# x15.net
KiCad netlist of a schematic drawn in EAGLE
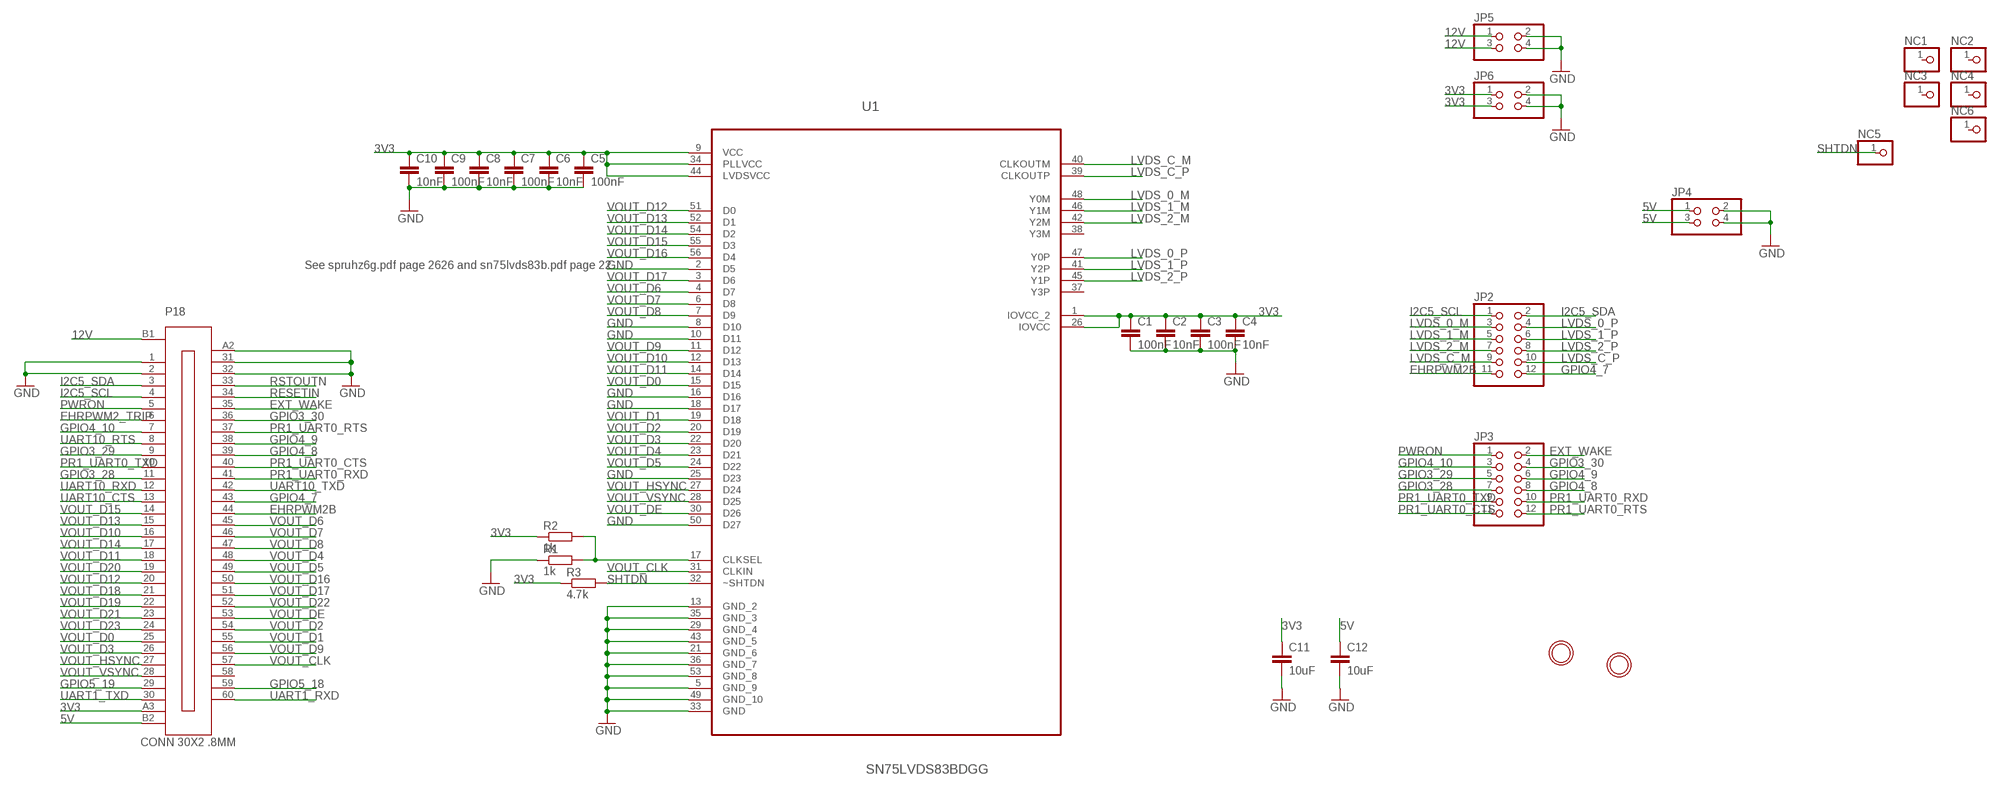
[diagram p0: schematic, sheet 1]

(export (version "E")
  (design (tool "Eeschema 10.0.6"))
  (components
    (comp (ref "C1")
      (value "100nF")
      (footprint "eagle-import:C0603K")
      (libsource (lib "eagle-import") (part "C-EUC0603K"))
    )
    (comp (ref "C2")
      (value "10nF")
      (footprint "eagle-import:C0603K")
      (libsource (lib "eagle-import") (part "C-EUC0603K"))
    )
    (comp (ref "C3")
      (value "100nF")
      (footprint "eagle-import:C0603K")
      (libsource (lib "eagle-import") (part "C-EUC0603K"))
    )
    (comp (ref "C4")
      (value "10nF")
      (footprint "eagle-import:C0603K")
      (libsource (lib "eagle-import") (part "C-EUC0603K"))
    )
    (comp (ref "C5")
      (value "100nF")
      (footprint "eagle-import:C0603K")
      (libsource (lib "eagle-import") (part "C-EUC0603K"))
    )
    (comp (ref "C6")
      (value "10nF")
      (footprint "eagle-import:C0603K")
      (libsource (lib "eagle-import") (part "C-EUC0603K"))
    )
    (comp (ref "C7")
      (value "100nF")
      (footprint "eagle-import:C0603K")
      (libsource (lib "eagle-import") (part "C-EUC0603K"))
    )
    (comp (ref "C8")
      (value "10nF")
      (footprint "eagle-import:C0603K")
      (libsource (lib "eagle-import") (part "C-EUC0603K"))
    )
    (comp (ref "C9")
      (value "100nF")
      (footprint "eagle-import:C0603K")
      (libsource (lib "eagle-import") (part "C-EUC0603K"))
    )
    (comp (ref "C10")
      (value "10nF")
      (footprint "eagle-import:C0603K")
      (libsource (lib "eagle-import") (part "C-EUC0603K"))
    )
    (comp (ref "C11")
      (value "10uF")
      (footprint "eagle-import:C1206K")
      (libsource (lib "eagle-import") (part "C-EUC1206K"))
    )
    (comp (ref "C12")
      (value "10uF")
      (footprint "eagle-import:C1206K")
      (libsource (lib "eagle-import") (part "C-EUC1206K"))
    )
    (comp (ref "JP2")
      (value "PINHD-2X6")
      (footprint "eagle-import:2X06")
      (libsource (lib "eagle-import") (part "PINHD-2X6"))
    )
    (comp (ref "JP3")
      (value "PINHD-2X6")
      (footprint "eagle-import:2X06")
      (libsource (lib "eagle-import") (part "PINHD-2X6"))
    )
    (comp (ref "JP4")
      (value "PINHD-2X2")
      (footprint "eagle-import:2X02")
      (libsource (lib "eagle-import") (part "PINHD-2X2"))
    )
    (comp (ref "JP5")
      (value "PINHD-2X2")
      (footprint "eagle-import:2X02")
      (libsource (lib "eagle-import") (part "PINHD-2X2"))
    )
    (comp (ref "JP6")
      (value "PINHD-2X2")
      (footprint "eagle-import:2X02")
      (libsource (lib "eagle-import") (part "PINHD-2X2"))
    )
    (comp (ref "NC1")
      (value "PINHD-1X1")
      (footprint "eagle-import:1X01")
      (libsource (lib "eagle-import") (part "PINHD-1X1"))
    )
    (comp (ref "NC2")
      (value "PINHD-1X1")
      (footprint "eagle-import:1X01")
      (libsource (lib "eagle-import") (part "PINHD-1X1"))
    )
    (comp (ref "NC3")
      (value "PINHD-1X1")
      (footprint "eagle-import:1X01")
      (libsource (lib "eagle-import") (part "PINHD-1X1"))
    )
    (comp (ref "NC4")
      (value "PINHD-1X1")
      (footprint "eagle-import:1X01")
      (libsource (lib "eagle-import") (part "PINHD-1X1"))
    )
    (comp (ref "NC5")
      (value "PINHD-1X1")
      (footprint "eagle-import:1X01")
      (libsource (lib "eagle-import") (part "PINHD-1X1"))
    )
    (comp (ref "NC6")
      (value "PINHD-1X1")
      (footprint "eagle-import:1X01")
      (libsource (lib "eagle-import") (part "PINHD-1X1"))
    )
    (comp (ref "P18")
      (value "CONN 30X2 .8MM")
      (footprint "eagle-import:CONN_FX18-60S-0.8SV15")
      (libsource (lib "eagle-import") (part "CONN_FX18-60?-0.8SSV15"))
    )
    (comp (ref "R1")
      (value "1k")
      (footprint "eagle-import:R0603")
      (libsource (lib "eagle-import") (part "R-EU_R0603"))
    )
    (comp (ref "R2")
      (value "1k")
      (footprint "eagle-import:R0603")
      (libsource (lib "eagle-import") (part "R-EU_R0603"))
    )
    (comp (ref "R3")
      (value "4.7k")
      (footprint "eagle-import:R0603")
      (libsource (lib "eagle-import") (part "R-EU_R0603"))
    )
    (comp (ref "U$1")
      (value "MOUNTINGHOLE2.5")
      (footprint "eagle-import:MOUNTINGHOLE_2.5_PLATED")
      (libsource (lib "eagle-import") (part "MOUNTINGHOLE2.5"))
    )
    (comp (ref "U$2")
      (value "MOUNTINGHOLE2.5")
      (footprint "eagle-import:MOUNTINGHOLE_2.5_PLATED")
      (libsource (lib "eagle-import") (part "MOUNTINGHOLE2.5"))
    )
    (comp (ref "U1")
      (value "SN75LVDS83BDGG")
      (footprint "eagle-import:SOP50P810X120-56N")
      (libsource (lib "eagle-import") (part "SN75LVDS83BDGG"))
    )
  )
  (nets
    (net (code "1") (name "/3V3") (class "Default")
      (node (ref "C1") (pin "1") (pinfunction "1_1") (pintype "passive"))
      (node (ref "C10") (pin "1") (pinfunction "1_1") (pintype "passive"))
      (node (ref "C11") (pin "1") (pinfunction "1_1") (pintype "passive"))
      (node (ref "C2") (pin "1") (pinfunction "1_1") (pintype "passive"))
      (node (ref "C3") (pin "1") (pinfunction "1_1") (pintype "passive"))
      (node (ref "C4") (pin "1") (pinfunction "1_1") (pintype "passive"))
      (node (ref "C5") (pin "1") (pinfunction "1_1") (pintype "passive"))
      (node (ref "C6") (pin "1") (pinfunction "1_1") (pintype "passive"))
      (node (ref "C7") (pin "1") (pinfunction "1_1") (pintype "passive"))
      (node (ref "C8") (pin "1") (pinfunction "1_1") (pintype "passive"))
      (node (ref "C9") (pin "1") (pinfunction "1_1") (pintype "passive"))
      (node (ref "JP6") (pin "1") (pinfunction "1_1") (pintype "passive"))
      (node (ref "JP6") (pin "3") (pinfunction "3_3") (pintype "passive"))
      (node (ref "P18") (pin "A3") (pinfunction "A3_A3") (pintype "bidirectional"))
      (node (ref "R2") (pin "1") (pinfunction "1_1") (pintype "passive"))
      (node (ref "R3") (pin "1") (pinfunction "1_1") (pintype "passive"))
      (node (ref "U1") (pin "1") (pinfunction "IOVCC_2_1") (pintype "output"))
      (node (ref "U1") (pin "26") (pinfunction "IOVCC_26") (pintype "output"))
      (node (ref "U1") (pin "34") (pinfunction "PLLVCC_34") (pintype "input"))
      (node (ref "U1") (pin "44") (pinfunction "LVDSVCC_44") (pintype "input"))
      (node (ref "U1") (pin "9") (pinfunction "VCC_9") (pintype "input"))
    )
    (net (code "2") (name "/5V") (class "Default")
      (node (ref "C12") (pin "1") (pinfunction "1_1") (pintype "passive"))
      (node (ref "JP4") (pin "1") (pinfunction "1_1") (pintype "passive"))
      (node (ref "JP4") (pin "3") (pinfunction "3_3") (pintype "passive"))
      (node (ref "P18") (pin "B2") (pinfunction "B2_B2") (pintype "bidirectional"))
    )
    (net (code "3") (name "/12V") (class "Default")
      (node (ref "JP5") (pin "1") (pinfunction "1_1") (pintype "passive"))
      (node (ref "JP5") (pin "3") (pinfunction "3_3") (pintype "passive"))
      (node (ref "P18") (pin "B1") (pinfunction "B1_B1") (pintype "bidirectional"))
    )
    (net (code "4") (name "/EHRPWM2B") (class "Default")
      (node (ref "JP2") (pin "11") (pinfunction "11_11") (pintype "passive"))
      (node (ref "P18") (pin "44") (pinfunction "44_44") (pintype "bidirectional"))
    )
    (net (code "5") (name "/EHRPWM2_TRIP") (class "Default")
      (node (ref "P18") (pin "6") (pinfunction "6_6") (pintype "bidirectional"))
    )
    (net (code "6") (name "/EXT_WAKE") (class "Default")
      (node (ref "JP3") (pin "2") (pinfunction "2_2") (pintype "passive"))
      (node (ref "P18") (pin "35") (pinfunction "35_35") (pintype "bidirectional"))
    )
    (net (code "7") (name "/GPIO3_28") (class "Default")
      (node (ref "JP3") (pin "7") (pinfunction "7_7") (pintype "passive"))
      (node (ref "P18") (pin "11") (pinfunction "11_11") (pintype "bidirectional"))
    )
    (net (code "8") (name "/GPIO3_29") (class "Default")
      (node (ref "JP3") (pin "5") (pinfunction "5_5") (pintype "passive"))
      (node (ref "P18") (pin "9") (pinfunction "9_9") (pintype "bidirectional"))
    )
    (net (code "9") (name "/GPIO3_30") (class "Default")
      (node (ref "JP3") (pin "4") (pinfunction "4_4") (pintype "passive"))
      (node (ref "P18") (pin "36") (pinfunction "36_36") (pintype "bidirectional"))
    )
    (net (code "10") (name "/GPIO4_7") (class "Default")
      (node (ref "JP2") (pin "12") (pinfunction "12_12") (pintype "passive"))
      (node (ref "P18") (pin "43") (pinfunction "43_43") (pintype "bidirectional"))
    )
    (net (code "11") (name "/GPIO4_8") (class "Default")
      (node (ref "JP3") (pin "8") (pinfunction "8_8") (pintype "passive"))
      (node (ref "P18") (pin "39") (pinfunction "39_39") (pintype "bidirectional"))
    )
    (net (code "12") (name "/GPIO4_9") (class "Default")
      (node (ref "JP3") (pin "6") (pinfunction "6_6") (pintype "passive"))
      (node (ref "P18") (pin "38") (pinfunction "38_38") (pintype "bidirectional"))
    )
    (net (code "13") (name "/GPIO4_10") (class "Default")
      (node (ref "JP3") (pin "3") (pinfunction "3_3") (pintype "passive"))
      (node (ref "P18") (pin "7") (pinfunction "7_7") (pintype "bidirectional"))
    )
    (net (code "14") (name "/GPIO5_18") (class "Default")
      (node (ref "P18") (pin "59") (pinfunction "59_59") (pintype "bidirectional"))
    )
    (net (code "15") (name "/GPIO5_19") (class "Default")
      (node (ref "P18") (pin "29") (pinfunction "29_29") (pintype "bidirectional"))
    )
    (net (code "16") (name "/I2C5_SCL") (class "Default")
      (node (ref "JP2") (pin "1") (pinfunction "1_1") (pintype "passive"))
      (node (ref "P18") (pin "4") (pinfunction "4_4") (pintype "bidirectional"))
    )
    (net (code "17") (name "/I2C5_SDA") (class "Default")
      (node (ref "JP2") (pin "2") (pinfunction "2_2") (pintype "passive"))
      (node (ref "P18") (pin "3") (pinfunction "3_3") (pintype "bidirectional"))
    )
    (net (code "18") (name "/LVDS_0_M") (class "Default")
      (node (ref "JP2") (pin "3") (pinfunction "3_3") (pintype "passive"))
      (node (ref "U1") (pin "48") (pinfunction "Y0M_48") (pintype "output"))
    )
    (net (code "19") (name "/LVDS_0_P") (class "Default")
      (node (ref "JP2") (pin "4") (pinfunction "4_4") (pintype "passive"))
      (node (ref "U1") (pin "47") (pinfunction "Y0P_47") (pintype "output"))
    )
    (net (code "20") (name "/LVDS_1_M") (class "Default")
      (node (ref "JP2") (pin "5") (pinfunction "5_5") (pintype "passive"))
      (node (ref "U1") (pin "46") (pinfunction "Y1M_46") (pintype "output"))
    )
    (net (code "21") (name "/LVDS_1_P") (class "Default")
      (node (ref "JP2") (pin "6") (pinfunction "6_6") (pintype "passive"))
      (node (ref "U1") (pin "41") (pinfunction "Y2P_41") (pintype "output"))
    )
    (net (code "22") (name "/LVDS_2_M") (class "Default")
      (node (ref "JP2") (pin "7") (pinfunction "7_7") (pintype "passive"))
      (node (ref "U1") (pin "42") (pinfunction "Y2M_42") (pintype "output"))
    )
    (net (code "23") (name "/LVDS_2_P") (class "Default")
      (node (ref "JP2") (pin "8") (pinfunction "8_8") (pintype "passive"))
      (node (ref "U1") (pin "45") (pinfunction "Y1P_45") (pintype "output"))
    )
    (net (code "24") (name "/LVDS_C_M") (class "Default")
      (node (ref "JP2") (pin "9") (pinfunction "9_9") (pintype "passive"))
      (node (ref "U1") (pin "40") (pinfunction "CLKOUTM_40") (pintype "output"))
    )
    (net (code "25") (name "/LVDS_C_P") (class "Default")
      (node (ref "JP2") (pin "10") (pinfunction "10_10") (pintype "passive"))
      (node (ref "U1") (pin "39") (pinfunction "CLKOUTP_39") (pintype "output"))
    )
    (net (code "26") (name "/PR1_UART0_CTS") (class "Default")
      (node (ref "JP3") (pin "11") (pinfunction "11_11") (pintype "passive"))
      (node (ref "P18") (pin "40") (pinfunction "40_40") (pintype "bidirectional"))
    )
    (net (code "27") (name "/PR1_UART0_RTS") (class "Default")
      (node (ref "JP3") (pin "12") (pinfunction "12_12") (pintype "passive"))
      (node (ref "P18") (pin "37") (pinfunction "37_37") (pintype "bidirectional"))
    )
    (net (code "28") (name "/PR1_UART0_RXD") (class "Default")
      (node (ref "JP3") (pin "10") (pinfunction "10_10") (pintype "passive"))
      (node (ref "P18") (pin "41") (pinfunction "41_41") (pintype "bidirectional"))
    )
    (net (code "29") (name "/PR1_UART0_TXD") (class "Default")
      (node (ref "JP3") (pin "9") (pinfunction "9_9") (pintype "passive"))
      (node (ref "P18") (pin "10") (pinfunction "10_10") (pintype "bidirectional"))
    )
    (net (code "30") (name "/PWRON") (class "Default")
      (node (ref "JP3") (pin "1") (pinfunction "1_1") (pintype "passive"))
      (node (ref "P18") (pin "5") (pinfunction "5_5") (pintype "bidirectional"))
    )
    (net (code "31") (name "/RESETIN") (class "Default")
      (node (ref "P18") (pin "34") (pinfunction "34_34") (pintype "bidirectional"))
    )
    (net (code "32") (name "/RSTOUTN") (class "Default")
      (node (ref "P18") (pin "33") (pinfunction "33_33") (pintype "bidirectional"))
    )
    (net (code "33") (name "/SHTDN") (class "Default")
      (node (ref "NC5") (pin "1") (pinfunction "1_1") (pintype "passive"))
      (node (ref "R3") (pin "2") (pinfunction "2_2") (pintype "passive"))
      (node (ref "U1") (pin "32") (pinfunction "~{SHTDN}_32") (pintype "input"))
    )
    (net (code "34") (name "/UART1_RXD") (class "Default")
      (node (ref "P18") (pin "60") (pinfunction "60_60") (pintype "bidirectional"))
    )
    (net (code "35") (name "/UART1_TXD") (class "Default")
      (node (ref "P18") (pin "30") (pinfunction "30_30") (pintype "bidirectional"))
    )
    (net (code "36") (name "/UART10_CTS") (class "Default")
      (node (ref "P18") (pin "13") (pinfunction "13_13") (pintype "bidirectional"))
    )
    (net (code "37") (name "/UART10_RTS") (class "Default")
      (node (ref "P18") (pin "8") (pinfunction "8_8") (pintype "bidirectional"))
    )
    (net (code "38") (name "/UART10_RXD") (class "Default")
      (node (ref "P18") (pin "12") (pinfunction "12_12") (pintype "bidirectional"))
    )
    (net (code "39") (name "/UART10_TXD") (class "Default")
      (node (ref "P18") (pin "42") (pinfunction "42_42") (pintype "bidirectional"))
    )
    (net (code "40") (name "/VOUT_CLK") (class "Default")
      (node (ref "P18") (pin "57") (pinfunction "57_57") (pintype "bidirectional"))
      (node (ref "U1") (pin "31") (pinfunction "CLKIN_31") (pintype "input"))
    )
    (net (code "41") (name "/VOUT_D0") (class "Default")
      (node (ref "P18") (pin "25") (pinfunction "25_25") (pintype "bidirectional"))
      (node (ref "U1") (pin "15") (pinfunction "D15_15") (pintype "input"))
    )
    (net (code "42") (name "/VOUT_D1") (class "Default")
      (node (ref "P18") (pin "55") (pinfunction "55_55") (pintype "bidirectional"))
      (node (ref "U1") (pin "19") (pinfunction "D18_19") (pintype "input"))
    )
    (net (code "43") (name "/VOUT_D2") (class "Default")
      (node (ref "P18") (pin "54") (pinfunction "54_54") (pintype "bidirectional"))
      (node (ref "U1") (pin "20") (pinfunction "D19_20") (pintype "input"))
    )
    (net (code "44") (name "/VOUT_D3") (class "Default")
      (node (ref "P18") (pin "26") (pinfunction "26_26") (pintype "bidirectional"))
      (node (ref "U1") (pin "22") (pinfunction "D20_22") (pintype "input"))
    )
    (net (code "45") (name "/VOUT_D4") (class "Default")
      (node (ref "P18") (pin "48") (pinfunction "48_48") (pintype "bidirectional"))
      (node (ref "U1") (pin "23") (pinfunction "D21_23") (pintype "input"))
    )
    (net (code "46") (name "/VOUT_D5") (class "Default")
      (node (ref "P18") (pin "49") (pinfunction "49_49") (pintype "bidirectional"))
      (node (ref "U1") (pin "24") (pinfunction "D22_24") (pintype "input"))
    )
    (net (code "47") (name "/VOUT_D6") (class "Default")
      (node (ref "P18") (pin "45") (pinfunction "45_45") (pintype "bidirectional"))
      (node (ref "U1") (pin "4") (pinfunction "D7_4") (pintype "input"))
    )
    (net (code "48") (name "/VOUT_D7") (class "Default")
      (node (ref "P18") (pin "46") (pinfunction "46_46") (pintype "bidirectional"))
      (node (ref "U1") (pin "6") (pinfunction "D8_6") (pintype "input"))
    )
    (net (code "49") (name "/VOUT_D8") (class "Default")
      (node (ref "P18") (pin "47") (pinfunction "47_47") (pintype "bidirectional"))
      (node (ref "U1") (pin "7") (pinfunction "D9_7") (pintype "input"))
    )
    (net (code "50") (name "/VOUT_D9") (class "Default")
      (node (ref "P18") (pin "56") (pinfunction "56_56") (pintype "bidirectional"))
      (node (ref "U1") (pin "11") (pinfunction "D12_11") (pintype "input"))
    )
    (net (code "51") (name "/VOUT_D10") (class "Default")
      (node (ref "P18") (pin "16") (pinfunction "16_16") (pintype "bidirectional"))
      (node (ref "U1") (pin "12") (pinfunction "D13_12") (pintype "input"))
    )
    (net (code "52") (name "/VOUT_D11") (class "Default")
      (node (ref "P18") (pin "18") (pinfunction "18_18") (pintype "bidirectional"))
      (node (ref "U1") (pin "14") (pinfunction "D14_14") (pintype "input"))
    )
    (net (code "53") (name "/VOUT_D12") (class "Default")
      (node (ref "P18") (pin "20") (pinfunction "20_20") (pintype "bidirectional"))
      (node (ref "U1") (pin "51") (pinfunction "D0_51") (pintype "output"))
    )
    (net (code "54") (name "/VOUT_D13") (class "Default")
      (node (ref "P18") (pin "15") (pinfunction "15_15") (pintype "bidirectional"))
      (node (ref "U1") (pin "52") (pinfunction "D1_52") (pintype "input"))
    )
    (net (code "55") (name "/VOUT_D14") (class "Default")
      (node (ref "P18") (pin "17") (pinfunction "17_17") (pintype "bidirectional"))
      (node (ref "U1") (pin "54") (pinfunction "D2_54") (pintype "input"))
    )
    (net (code "56") (name "/VOUT_D15") (class "Default")
      (node (ref "P18") (pin "14") (pinfunction "14_14") (pintype "bidirectional"))
      (node (ref "U1") (pin "55") (pinfunction "D3_55") (pintype "input"))
    )
    (net (code "57") (name "/VOUT_D16") (class "Default")
      (node (ref "P18") (pin "50") (pinfunction "50_50") (pintype "bidirectional"))
      (node (ref "U1") (pin "56") (pinfunction "D4_56") (pintype "input"))
    )
    (net (code "58") (name "/VOUT_D17") (class "Default")
      (node (ref "P18") (pin "51") (pinfunction "51_51") (pintype "bidirectional"))
      (node (ref "U1") (pin "3") (pinfunction "D6_3") (pintype "input"))
    )
    (net (code "59") (name "/VOUT_D18") (class "Default")
      (node (ref "P18") (pin "21") (pinfunction "21_21") (pintype "bidirectional"))
    )
    (net (code "60") (name "/VOUT_D19") (class "Default")
      (node (ref "P18") (pin "22") (pinfunction "22_22") (pintype "bidirectional"))
    )
    (net (code "61") (name "/VOUT_D20") (class "Default")
      (node (ref "P18") (pin "19") (pinfunction "19_19") (pintype "bidirectional"))
    )
    (net (code "62") (name "/VOUT_D21") (class "Default")
      (node (ref "P18") (pin "23") (pinfunction "23_23") (pintype "bidirectional"))
    )
    (net (code "63") (name "/VOUT_D22") (class "Default")
      (node (ref "P18") (pin "52") (pinfunction "52_52") (pintype "bidirectional"))
    )
    (net (code "64") (name "/VOUT_D23") (class "Default")
      (node (ref "P18") (pin "24") (pinfunction "24_24") (pintype "bidirectional"))
    )
    (net (code "65") (name "/VOUT_DE") (class "Default")
      (node (ref "P18") (pin "53") (pinfunction "53_53") (pintype "bidirectional"))
      (node (ref "U1") (pin "30") (pinfunction "D26_30") (pintype "input"))
    )
    (net (code "66") (name "/VOUT_HSYNC") (class "Default")
      (node (ref "P18") (pin "27") (pinfunction "27_27") (pintype "bidirectional"))
      (node (ref "U1") (pin "27") (pinfunction "D24_27") (pintype "input"))
    )
    (net (code "67") (name "/VOUT_VSYNC") (class "Default")
      (node (ref "P18") (pin "28") (pinfunction "28_28") (pintype "bidirectional"))
      (node (ref "U1") (pin "28") (pinfunction "D25_28") (pintype "input"))
    )
    (net (code "68") (name "GND") (class "Default")
      (node (ref "C1") (pin "2") (pinfunction "2_2") (pintype "passive"))
      (node (ref "C10") (pin "2") (pinfunction "2_2") (pintype "passive"))
      (node (ref "C11") (pin "2") (pinfunction "2_2") (pintype "passive"))
      (node (ref "C12") (pin "2") (pinfunction "2_2") (pintype "passive"))
      (node (ref "C2") (pin "2") (pinfunction "2_2") (pintype "passive"))
      (node (ref "C3") (pin "2") (pinfunction "2_2") (pintype "passive"))
      (node (ref "C4") (pin "2") (pinfunction "2_2") (pintype "passive"))
      (node (ref "C5") (pin "2") (pinfunction "2_2") (pintype "passive"))
      (node (ref "C6") (pin "2") (pinfunction "2_2") (pintype "passive"))
      (node (ref "C7") (pin "2") (pinfunction "2_2") (pintype "passive"))
      (node (ref "C8") (pin "2") (pinfunction "2_2") (pintype "passive"))
      (node (ref "C9") (pin "2") (pinfunction "2_2") (pintype "passive"))
      (node (ref "JP4") (pin "2") (pinfunction "2_2") (pintype "passive"))
      (node (ref "JP4") (pin "4") (pinfunction "4_4") (pintype "passive"))
      (node (ref "JP5") (pin "2") (pinfunction "2_2") (pintype "passive"))
      (node (ref "JP5") (pin "4") (pinfunction "4_4") (pintype "passive"))
      (node (ref "JP6") (pin "2") (pinfunction "2_2") (pintype "passive"))
      (node (ref "JP6") (pin "4") (pinfunction "4_4") (pintype "passive"))
      (node (ref "P18") (pin "1") (pinfunction "1_1") (pintype "bidirectional"))
      (node (ref "P18") (pin "2") (pinfunction "2_2") (pintype "bidirectional"))
      (node (ref "P18") (pin "31") (pinfunction "31_31") (pintype "bidirectional"))
      (node (ref "P18") (pin "32") (pinfunction "32_32") (pintype "bidirectional"))
      (node (ref "P18") (pin "A2") (pinfunction "A2_A2") (pintype "bidirectional"))
      (node (ref "R1") (pin "1") (pinfunction "1_1") (pintype "passive"))
      (node (ref "U1") (pin "10") (pinfunction "D11_10") (pintype "input"))
      (node (ref "U1") (pin "13") (pinfunction "GND_2_13") (pintype "passive"))
      (node (ref "U1") (pin "16") (pinfunction "D16_16") (pintype "input"))
      (node (ref "U1") (pin "18") (pinfunction "D17_18") (pintype "input"))
      (node (ref "U1") (pin "2") (pinfunction "D5_2") (pintype "input"))
      (node (ref "U1") (pin "21") (pinfunction "GND_6_21") (pintype "passive"))
      (node (ref "U1") (pin "25") (pinfunction "D23_25") (pintype "input"))
      (node (ref "U1") (pin "29") (pinfunction "GND_4_29") (pintype "passive"))
      (node (ref "U1") (pin "33") (pinfunction "GND_33") (pintype "passive"))
      (node (ref "U1") (pin "35") (pinfunction "GND_3_35") (pintype "passive"))
      (node (ref "U1") (pin "36") (pinfunction "GND_7_36") (pintype "passive"))
      (node (ref "U1") (pin "43") (pinfunction "GND_5_43") (pintype "passive"))
      (node (ref "U1") (pin "49") (pinfunction "GND_10_49") (pintype "passive"))
      (node (ref "U1") (pin "5") (pinfunction "GND_9_5") (pintype "passive"))
      (node (ref "U1") (pin "50") (pinfunction "D27_50") (pintype "output"))
      (node (ref "U1") (pin "53") (pinfunction "GND_8_53") (pintype "passive"))
      (node (ref "U1") (pin "8") (pinfunction "D10_8") (pintype "input"))
    )
    (net (code "69") (name "Net-(U1-CLKSEL)") (class "Default")
      (node (ref "R1") (pin "2") (pinfunction "2_2") (pintype "passive"))
      (node (ref "R2") (pin "2") (pinfunction "2_2") (pintype "passive"))
      (node (ref "U1") (pin "17") (pinfunction "CLKSEL_17") (pintype "input"))
    )
    (net (code "70") (name "unconnected-(NC1-Pad1)") (class "Default")
      (node (ref "NC1") (pin "1") (pinfunction "1_1") (pintype "passive"))
    )
    (net (code "71") (name "unconnected-(NC2-Pad1)") (class "Default")
      (node (ref "NC2") (pin "1") (pinfunction "1_1") (pintype "passive"))
    )
    (net (code "72") (name "unconnected-(NC3-Pad1)") (class "Default")
      (node (ref "NC3") (pin "1") (pinfunction "1_1") (pintype "passive"))
    )
    (net (code "73") (name "unconnected-(NC4-Pad1)") (class "Default")
      (node (ref "NC4") (pin "1") (pinfunction "1_1") (pintype "passive"))
    )
    (net (code "74") (name "unconnected-(NC6-Pad1)") (class "Default")
      (node (ref "NC6") (pin "1") (pinfunction "1_1") (pintype "passive"))
    )
    (net (code "75") (name "unconnected-(P18-Pad58)") (class "Default")
      (node (ref "P18") (pin "58") (pinfunction "58_58") (pintype "bidirectional"))
    )
    (net (code "76") (name "unconnected-(U1-Y3M-Pad38)") (class "Default")
      (node (ref "U1") (pin "38") (pinfunction "Y3M_38") (pintype "output"))
    )
    (net (code "77") (name "unconnected-(U1-Y3P-Pad37)") (class "Default")
      (node (ref "U1") (pin "37") (pinfunction "Y3P_37") (pintype "output"))
    )
  )
)
